# current_sense.net
KiCad netlist of a schematic drawn in Altium Designer
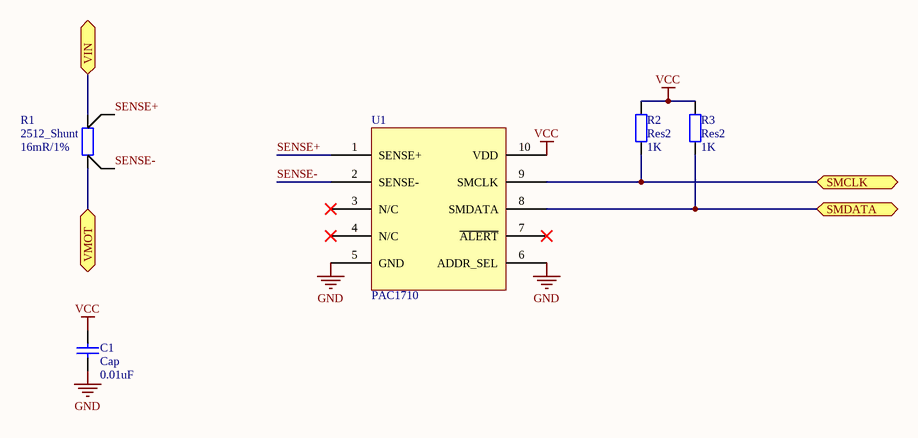
[diagram p0: current_sense.SchDoc]

(export (version "E")
  (design (tool "Eeschema 10.0.6"))
  (components
    (comp (ref "C1")
      (value "Cap")
      (footprint "RAD-0.3")
      (description "Capacitor")
      (fields (field (name "ALTIUM_VALUE") "0.01uF") (field (name "PUBLISHER") "Altium Limited"))
      (libsource (lib "Miscellaneous Devices") (part "Cap"))
    )
    (comp (ref "R1")
      (value "16mR/1%")
      (footprint "SMD_Resistor-shunt_2512")
      (description "TE CONNECTIVITY  352115RFT  RESISTOR, 2512, 2W, 15R, 1%")
      (fields
        (field (name "MANUFACTURER") "TE CONNECTIVITY")
        (field (name "MANUFACTURERPARTNUMBER") "352115RFT")
        (field (name "PACKAGE") "2512_Shunt")
      )
      (libsource (lib "motee_v2") (part "352115RFT"))
    )
    (comp (ref "R2")
      (value "Res2")
      (footprint "AXIAL-0.4")
      (description "Resistor")
      (fields (field (name "ALTIUM_VALUE") "1K") (field (name "PUBLISHER") "Altium Limited"))
      (libsource (lib "Miscellaneous Devices") (part "Res2"))
    )
    (comp (ref "R3")
      (value "Res2")
      (footprint "AXIAL-0.4")
      (description "Resistor")
      (fields (field (name "ALTIUM_VALUE") "1K") (field (name "PUBLISHER") "Altium Limited"))
      (libsource (lib "Miscellaneous Devices") (part "Res2"))
    )
    (comp (ref "U1") (value "PAC1710") (libsource (lib "motee_v2") (part "PAC1710")))
  )
  (nets
    (net (code "1") (name "/SENSE+") (class "Default")
      (node (ref "R1") (pin "3") (pinfunction "3_3") (pintype "passive"))
      (node (ref "U1") (pin "1") (pinfunction "SENSE+_1") (pintype "passive"))
    )
    (net (code "2") (name "/SENSE-") (class "Default")
      (node (ref "R1") (pin "2") (pinfunction "2_2") (pintype "passive"))
      (node (ref "U1") (pin "2") (pinfunction "SENSE-_2") (pintype "passive"))
    )
    (net (code "3") (name "/SMCLK") (class "Default")
      (node (ref "R2") (pin "1") (pinfunction "1_1") (pintype "passive"))
      (node (ref "U1") (pin "9") (pinfunction "SMCLK_9") (pintype "passive"))
    )
    (net (code "4") (name "/SMDATA") (class "Default")
      (node (ref "R3") (pin "1") (pinfunction "1_1") (pintype "passive"))
      (node (ref "U1") (pin "8") (pinfunction "SMDATA_8") (pintype "passive"))
    )
    (net (code "5") (name "/VIN") (class "Default")
      (node (ref "R1") (pin "4") (pinfunction "4_4") (pintype "passive"))
    )
    (net (code "6") (name "/VMOT") (class "Default")
      (node (ref "R1") (pin "1") (pinfunction "1_1") (pintype "passive"))
    )
    (net (code "7") (name "GND") (class "Default")
      (node (ref "C1") (pin "1") (pinfunction "1_1") (pintype "passive"))
      (node (ref "U1") (pin "5") (pinfunction "GND_5") (pintype "passive"))
      (node (ref "U1") (pin "6") (pinfunction "ADDR_SEL_6") (pintype "passive"))
    )
    (net (code "8") (name "VCC") (class "Default")
      (node (ref "C1") (pin "2") (pinfunction "2_2") (pintype "passive"))
      (node (ref "R2") (pin "2") (pinfunction "2_2") (pintype "passive"))
      (node (ref "R3") (pin "2") (pinfunction "2_2") (pintype "passive"))
      (node (ref "U1") (pin "10") (pinfunction "VDD_10") (pintype "passive"))
    )
    (net (code "9") (name "unconnected-(U1-N{slash}C-Pad3)") (class "Default")
      (node (ref "U1") (pin "3") (pinfunction "N/C_3") (pintype "passive+no_connect"))
    )
    (net (code "10") (name "unconnected-(U1-N{slash}C-Pad4)") (class "Default")
      (node (ref "U1") (pin "4") (pinfunction "N/C_4") (pintype "passive+no_connect"))
    )
    (net (code "11") (name "unconnected-(U1-~{ALERT}-Pad7)") (class "Default")
      (node (ref "U1") (pin "7") (pinfunction "~{ALERT}_7") (pintype "passive+no_connect"))
    )
  )
)
